# 0234-carrier-level-shifter-x8.net
KiCad netlist of a schematic drawn in EAGLE
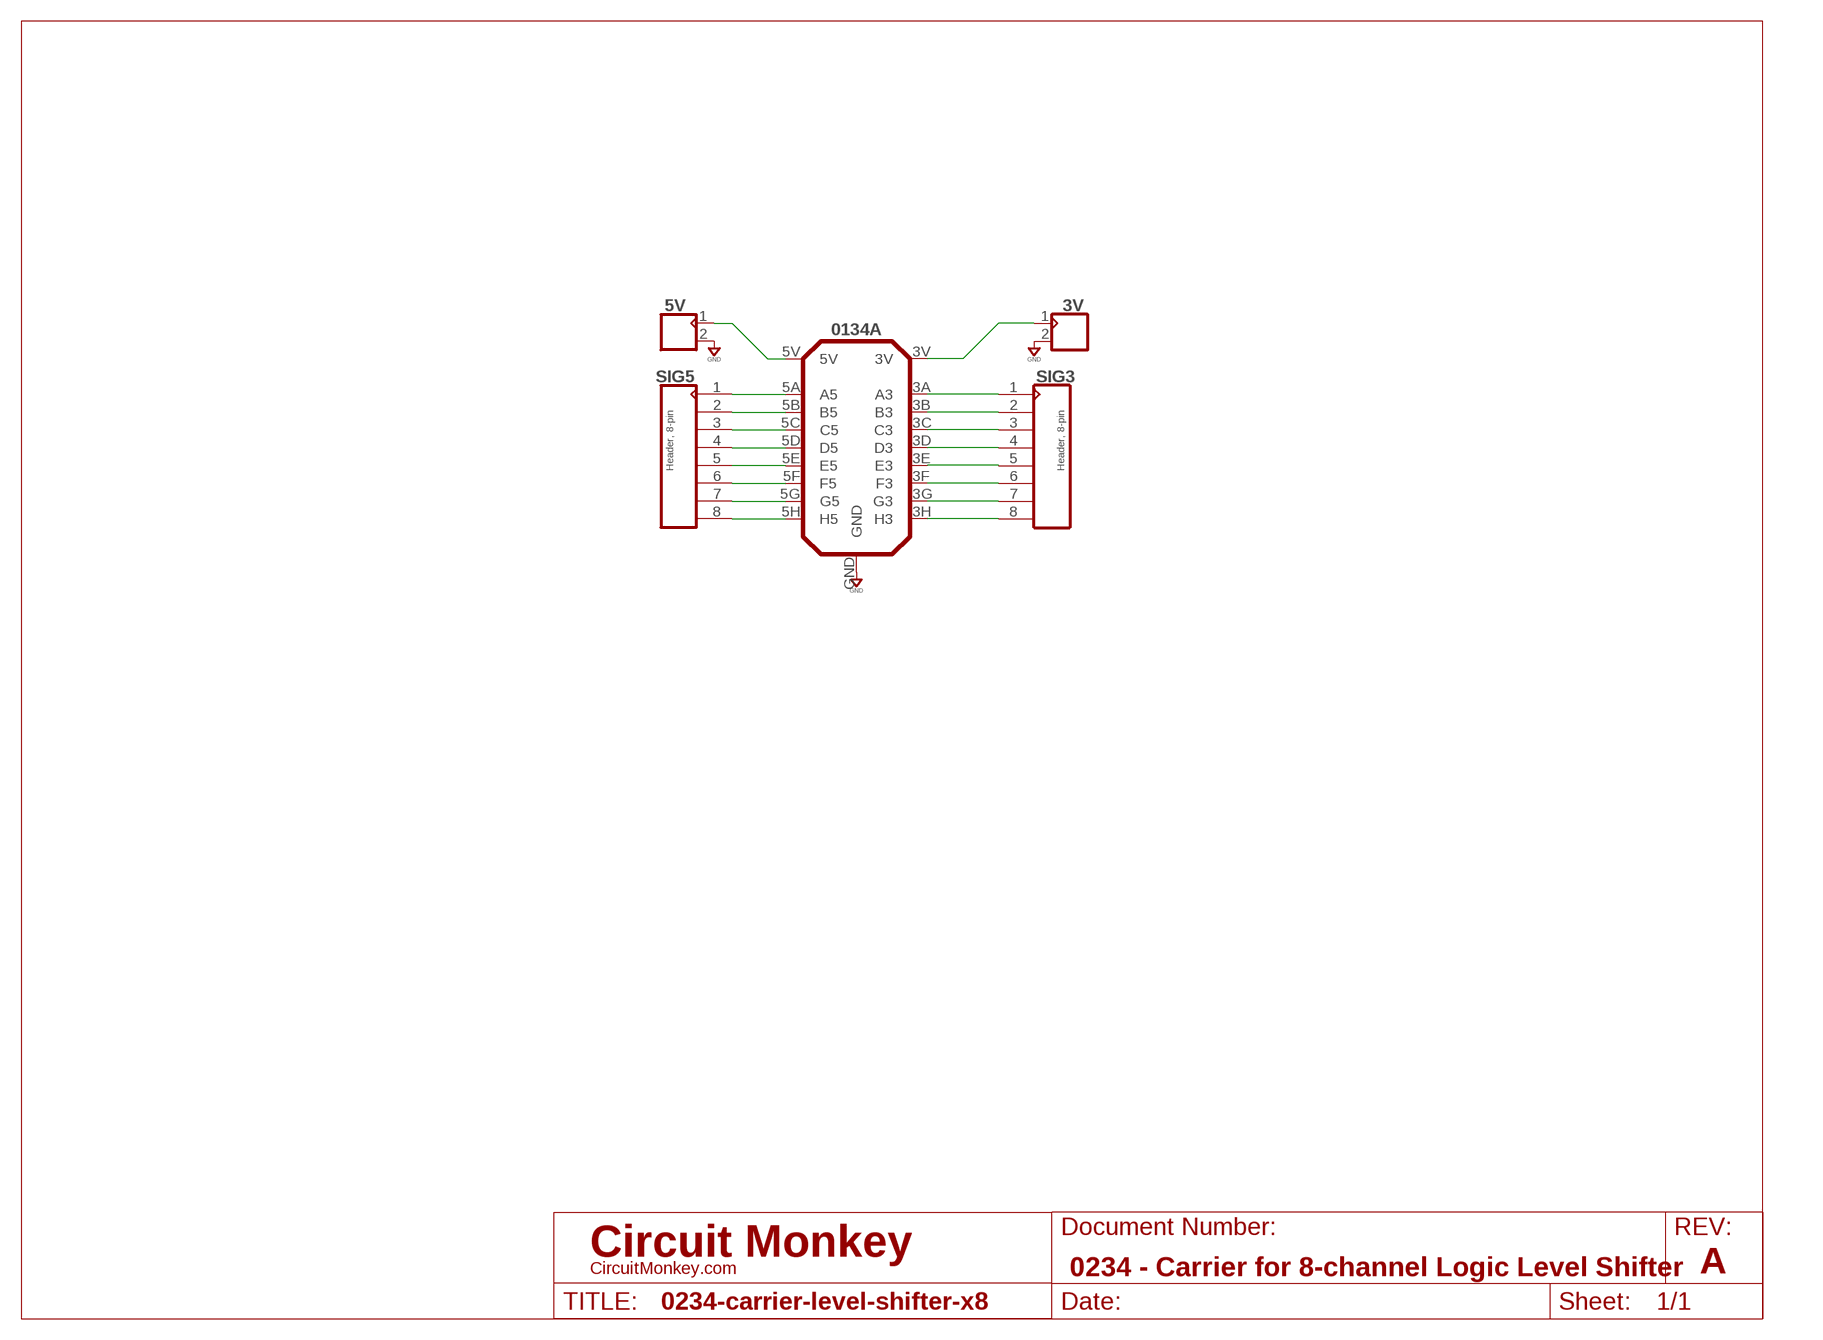
[diagram p0: schematic, sheet 1]

(export (version "E")
  (design (tool "Eeschema 10.0.6"))
  (components
    (comp (ref "3V")
      (value "CON_02X1-2.54MM-THD-VT")
      (footprint "eagle-import:MA02X1-VT-THD")
      (libsource (lib "eagle-import") (part "CON_02X1-2.54MM-THD-VT"))
    )
    (comp (ref "5V")
      (value "CON_02X1-2.54MM-THD-VT")
      (footprint "eagle-import:MA02X1-VT-THD")
      (libsource (lib "eagle-import") (part "CON_02X1-2.54MM-THD-VT"))
    )
    (comp (ref "0134A")
      (value "0134REV_A")
      (footprint "eagle-import:0134A")
      (libsource (lib "eagle-import") (part "0134REV_A"))
    )
    (comp (ref "SIG3")
      (value "Header, 8-pin")
      (footprint "eagle-import:MA08X1-VT-THD")
      (libsource (lib "eagle-import") (part "CON_08X1-VT-THD"))
    )
    (comp (ref "SIG5")
      (value "Header, 8-pin")
      (footprint "eagle-import:MA08X1-VT-THD")
      (libsource (lib "eagle-import") (part "CON_08X1-VT-THD"))
    )
  )
  (nets
    (net (code "1") (name "GND") (class "Default")
      (node (ref "0134A") (pin "GND") (pinfunction "GND_GND") (pintype "bidirectional"))
      (node (ref "3V") (pin "2") (pinfunction "2_2") (pintype "passive"))
      (node (ref "5V") (pin "2") (pinfunction "2_2") (pintype "passive"))
    )
    (net (code "2") (name "Net-(0134A-A3)") (class "Default")
      (node (ref "0134A") (pin "3A") (pinfunction "A3_3A") (pintype "bidirectional"))
      (node (ref "SIG3") (pin "1") (pinfunction "1_1") (pintype "passive"))
    )
    (net (code "3") (name "Net-(0134A-A5)") (class "Default")
      (node (ref "0134A") (pin "5A") (pinfunction "A5_5A") (pintype "bidirectional"))
      (node (ref "SIG5") (pin "1") (pinfunction "1_1") (pintype "passive"))
    )
    (net (code "4") (name "Net-(0134A-B3)") (class "Default")
      (node (ref "0134A") (pin "3B") (pinfunction "B3_3B") (pintype "bidirectional"))
      (node (ref "SIG3") (pin "2") (pinfunction "2_2") (pintype "passive"))
    )
    (net (code "5") (name "Net-(0134A-B5)") (class "Default")
      (node (ref "0134A") (pin "5B") (pinfunction "B5_5B") (pintype "bidirectional"))
      (node (ref "SIG5") (pin "2") (pinfunction "2_2") (pintype "passive"))
    )
    (net (code "6") (name "Net-(0134A-C3)") (class "Default")
      (node (ref "0134A") (pin "3C") (pinfunction "C3_3C") (pintype "bidirectional"))
      (node (ref "SIG3") (pin "3") (pinfunction "3_3") (pintype "passive"))
    )
    (net (code "7") (name "Net-(0134A-C5)") (class "Default")
      (node (ref "0134A") (pin "5C") (pinfunction "C5_5C") (pintype "bidirectional"))
      (node (ref "SIG5") (pin "3") (pinfunction "3_3") (pintype "passive"))
    )
    (net (code "8") (name "Net-(0134A-D3)") (class "Default")
      (node (ref "0134A") (pin "3D") (pinfunction "D3_3D") (pintype "bidirectional"))
      (node (ref "SIG3") (pin "4") (pinfunction "4_4") (pintype "passive"))
    )
    (net (code "9") (name "Net-(0134A-D5)") (class "Default")
      (node (ref "0134A") (pin "5D") (pinfunction "D5_5D") (pintype "bidirectional"))
      (node (ref "SIG5") (pin "4") (pinfunction "4_4") (pintype "passive"))
    )
    (net (code "10") (name "Net-(0134A-E3)") (class "Default")
      (node (ref "0134A") (pin "3E") (pinfunction "E3_3E") (pintype "bidirectional"))
      (node (ref "SIG3") (pin "5") (pinfunction "5_5") (pintype "passive"))
    )
    (net (code "11") (name "Net-(0134A-E5)") (class "Default")
      (node (ref "0134A") (pin "5E") (pinfunction "E5_5E") (pintype "bidirectional"))
      (node (ref "SIG5") (pin "5") (pinfunction "5_5") (pintype "passive"))
    )
    (net (code "12") (name "Net-(0134A-F3)") (class "Default")
      (node (ref "0134A") (pin "3F") (pinfunction "F3_3F") (pintype "bidirectional"))
      (node (ref "SIG3") (pin "6") (pinfunction "6_6") (pintype "passive"))
    )
    (net (code "13") (name "Net-(0134A-F5)") (class "Default")
      (node (ref "0134A") (pin "5F") (pinfunction "F5_5F") (pintype "bidirectional"))
      (node (ref "SIG5") (pin "6") (pinfunction "6_6") (pintype "passive"))
    )
    (net (code "14") (name "Net-(0134A-G3)") (class "Default")
      (node (ref "0134A") (pin "3G") (pinfunction "G3_3G") (pintype "bidirectional"))
      (node (ref "SIG3") (pin "7") (pinfunction "7_7") (pintype "passive"))
    )
    (net (code "15") (name "Net-(0134A-G5)") (class "Default")
      (node (ref "0134A") (pin "5G") (pinfunction "G5_5G") (pintype "bidirectional"))
      (node (ref "SIG5") (pin "7") (pinfunction "7_7") (pintype "passive"))
    )
    (net (code "16") (name "Net-(0134A-H3)") (class "Default")
      (node (ref "0134A") (pin "3H") (pinfunction "H3_3H") (pintype "bidirectional"))
      (node (ref "SIG3") (pin "8") (pinfunction "8_8") (pintype "passive"))
    )
    (net (code "17") (name "Net-(0134A-H5)") (class "Default")
      (node (ref "0134A") (pin "5H") (pinfunction "H5_5H") (pintype "bidirectional"))
      (node (ref "SIG5") (pin "8") (pinfunction "8_8") (pintype "passive"))
    )
    (net (code "18") (name "Net-(0134A-Pad3V)") (class "Default")
      (node (ref "0134A") (pin "3V") (pinfunction "3V_3V") (pintype "bidirectional"))
      (node (ref "3V") (pin "1") (pinfunction "1_1") (pintype "passive"))
    )
    (net (code "19") (name "Net-(0134A-Pad5V)") (class "Default")
      (node (ref "0134A") (pin "5V") (pinfunction "5V_5V") (pintype "bidirectional"))
      (node (ref "5V") (pin "1") (pinfunction "1_1") (pintype "passive"))
    )
  )
)
